# candle.net
KiCad netlist of a schematic drawn in EAGLE
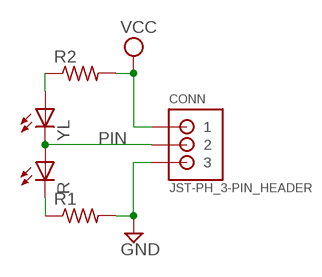
[diagram p0: schematic, sheet 1]

(export (version "E")
  (design (tool "Eeschema 10.0.6"))
  (components
    (comp (ref "CONN")
      (value "JST-PH_3-PIN_HEADER")
      (footprint "eagle-import:JST_B3B-PH_HEADER")
      (libsource (lib "eagle-import") (part "JST-PH_3-PIN_HEADER"))
    )
    (comp (ref "R")
      (value "LED3MM")
      (footprint "eagle-import:LED3MM")
      (libsource (lib "eagle-import") (part "LED3MM"))
    )
    (comp (ref "R1")
      (value "R-US_M1206")
      (footprint "eagle-import:M1206")
      (libsource (lib "eagle-import") (part "R-US_M1206"))
    )
    (comp (ref "R2")
      (value "R-US_M1206")
      (footprint "eagle-import:M1206")
      (libsource (lib "eagle-import") (part "R-US_M1206"))
    )
    (comp (ref "YL")
      (value "LED3MM")
      (footprint "eagle-import:LED3MM")
      (libsource (lib "eagle-import") (part "LED3MM"))
    )
  )
  (nets
    (net (code "1") (name "/PIN") (class "Default")
      (node (ref "CONN") (pin "P2") (pinfunction "2_P2") (pintype "bidirectional"))
      (node (ref "R") (pin "A") (pinfunction "A_A") (pintype "passive"))
      (node (ref "YL") (pin "K") (pinfunction "C_K") (pintype "passive"))
    )
    (net (code "2") (name "GND") (class "Default")
      (node (ref "CONN") (pin "P3") (pinfunction "3_P3") (pintype "bidirectional"))
      (node (ref "R1") (pin "2") (pinfunction "2_2") (pintype "passive"))
    )
    (net (code "3") (name "Net-(R-C)") (class "Default")
      (node (ref "R") (pin "K") (pinfunction "C_K") (pintype "passive"))
      (node (ref "R1") (pin "1") (pinfunction "1_1") (pintype "passive"))
    )
    (net (code "4") (name "Net-(R2-Pad1)") (class "Default")
      (node (ref "R2") (pin "1") (pinfunction "1_1") (pintype "passive"))
      (node (ref "YL") (pin "A") (pinfunction "A_A") (pintype "passive"))
    )
    (net (code "5") (name "VCC") (class "Default")
      (node (ref "CONN") (pin "P1") (pinfunction "1_P1") (pintype "bidirectional"))
      (node (ref "R2") (pin "2") (pinfunction "2_2") (pintype "passive"))
    )
  )
)
